# DC-DC_14V.net
KiCad netlist of a schematic drawn in Altium Designer
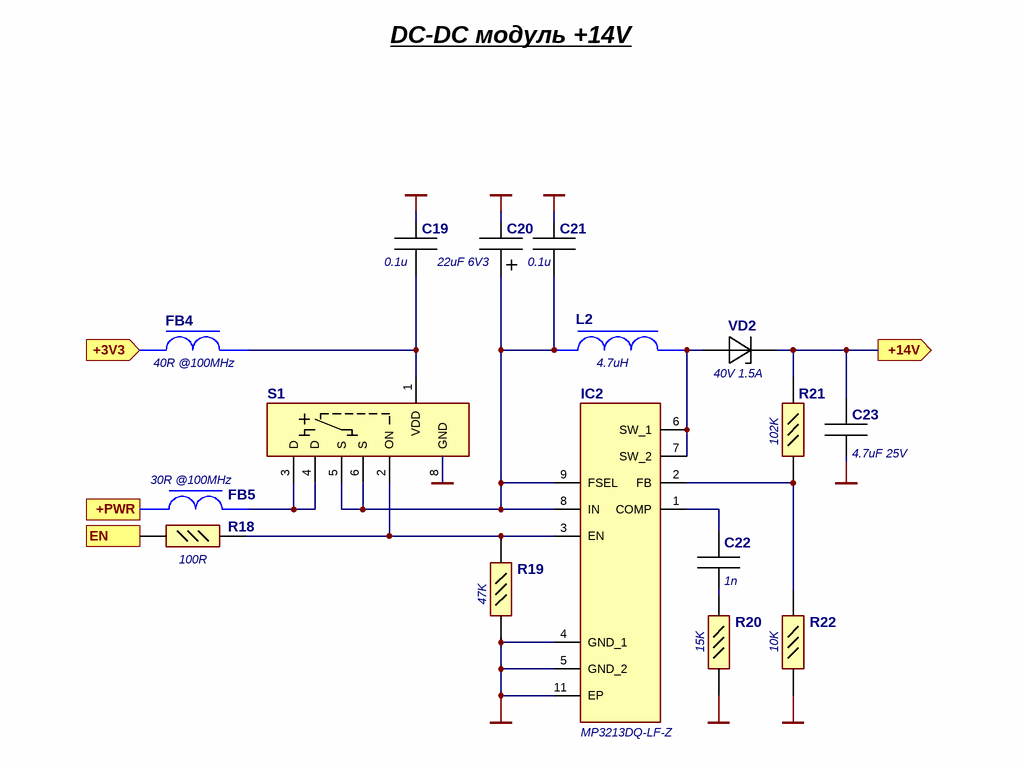
[diagram p0: DC-DC модуль +14V.SchDoc]

(export (version "E")
  (design (tool "Eeschema 10.0.6"))
  (components
    (comp (ref "C19")
      (value "0.1u")
      (footprint ":CAP0402 100x50x50")
      (description "±10% 25V Ceramic Capacitor X7R 0402 (1005 Metric)")
      (fields
        (field (name "MANUFACTURER_PART_NUMBER") "GRM155R71E104KE14J")
        (field (name "MOUSER PART NUMBER") "81-GRM155R71E104KE4J")
      )
      (libsource (lib "Capacitors 0402") (part "GRM155R71E104KE14J"))
    )
    (comp (ref "C20")
      (value "22uF 6V3")
      (footprint ":CAP1206 C3216-18")
      (description "22uF Molded Tantalum Capacitors 6.3V 1206 (3216 Metric) 300mOhm @ 100kHz")
      (fields (field (name "MANUFACTURER_PART_NUMBER") "TPSA226K006R0300"))
      (libsource (lib "Capacitors 1206") (part "TPSA226K006R0300"))
    )
    (comp (ref "C21")
      (value "0.1u")
      (footprint ":CAP0402 100x50x50")
      (description "±10% 25V Ceramic Capacitor X7R 0402 (1005 Metric)")
      (fields
        (field (name "MANUFACTURER_PART_NUMBER") "GRM155R71E104KE14J")
        (field (name "MOUSER PART NUMBER") "81-GRM155R71E104KE4J")
      )
      (libsource (lib "Capacitors 0402") (part "GRM155R71E104KE14J"))
    )
    (comp (ref "C22")
      (value "1n")
      (footprint ":CAP0402 100x50x50")
      (description "±5% 50V Ceramic Capacitor C0G, NP0 0402 (1005 Metric)")
      (fields (field (name "MANUFACTURER_PART_NUMBER") "GRM1555C1H102JA01J"))
      (libsource (lib "Capacitors 0402") (part "GRM1555C1H102JA01J"))
    )
    (comp (ref "C23")
      (value "4.7uF 25V")
      (footprint ":CAP0805 C2012X125")
      (description "CAP CER 4.7uF 25V X7R 0805")
      (fields (field (name "MANUFACTURER_PART_NUMBER") "GRM21BZ71E475KE15L"))
      (libsource (lib "Capacitors 0805") (part "GRM21BZ71E475KE15L"))
    )
    (comp (ref "FB4")
      (value "40R @100MHz")
      (footprint ":FER MMZ1005Y400CTD25")
      (description "40 Ohms @ 100MHz 1 Signal Line Ferrite Bead 0402 (1005 Metric) 550mA 100mOhm")
      (fields
        (field (name "MANUFACTURER_PART_NUMBER") "MMZ1005Y400CTD25")
        (field (name "MOUSER PART NUMBER") "810-MMZ1005Y400CTD25")
      )
      (libsource (lib "Ferrite Bead") (part "MMZ1005Y400CTD25"))
    )
    (comp (ref "FB5")
      (value "30R @100MHz")
      (footprint ":FER BLM18SP300SN1D")
      (description "30 Ohms @ 100MHz 1 Power Line Ferrite Bead 0603 (1608 Metric) 6A 8mOhm")
      (fields
        (field (name "MANUFACTURER_PART_NUMBER") "BLM18SP300SN1D")
        (field (name "MOUSER PART NUMBER") "81-BLM18SP300SN1D")
      )
      (libsource (lib "Ferrite Bead") (part "BLM18SP300SN1D"))
    )
    (comp (ref "IC2")
      (value "MP3213DQ-LF-Z")
      (footprint ":QFN10 P300X300X100-11N-D")
      (description "DC/DC Converter \r\n3...22V 3.5A")
      (fields (field (name "MOUSER PART NUMBER") "946-MP3213DQLFZ"))
      (libsource (lib "DC-DC convertors") (part "MP3213DQ-LF-Z"))
    )
    (comp (ref "L2")
      (value "4.7uH")
      (footprint ":IND1210 C3225")
      (fields (field (name "MANUFACTURER_PART_NUMBER") "CBC3225T4R7MR"))
      (libsource (lib "Inductance") (part "CBC3225T4R7MR"))
    )
    (comp (ref "R18")
      (value "RC0402FR-07")
      (footprint ":RES0402")
      (fields (field (name "MANUFACTURER_PART_NUMBER (PART 2: VALUE)") "100R"))
      (libsource (lib "") (part "RC0402FR-07_1"))
    )
    (comp (ref "R19")
      (value "RC0402FR-07")
      (footprint ":RES0402")
      (fields (field (name "MANUFACTURER_PART_NUMBER (PART 2: VALUE)") "47K"))
      (libsource (lib "Resistors 0402") (part "RC0402FR-07"))
    )
    (comp (ref "R20")
      (value "RC0402FR-07")
      (footprint ":RES0402")
      (fields (field (name "MANUFACTURER_PART_NUMBER (PART 2: VALUE)") "15K"))
      (libsource (lib "Resistors 0402") (part "RC0402FR-07"))
    )
    (comp (ref "R21")
      (value "RC0402FR-07")
      (footprint ":RES0402")
      (fields (field (name "MANUFACTURER_PART_NUMBER (PART 2: VALUE)") "102K"))
      (libsource (lib "Resistors 0402") (part "RC0402FR-07"))
    )
    (comp (ref "R22")
      (value "RC0402FR-07")
      (footprint ":RES0402")
      (fields (field (name "MANUFACTURER_PART_NUMBER (PART 2: VALUE)") "10K"))
      (libsource (lib "Resistors 0402") (part "RC0402FR-07"))
    )
    (comp (ref "S1")
      (value "4A 7.8mOhm")
      (footprint ":TRAN SLG59M309V")
      (description "Power Switch/Driver 1:1 N-Channel 4A  7.8mOhm 8-FC-TDFN (1.5x2)")
      (fields (field (name "MANUFACTURER_PART_NUMBER") "SLG59M309V"))
      (libsource (lib "Switching and Relays") (part "SLG59M309V"))
    )
    (comp (ref "VD2")
      (value "40V 1.5A")
      (footprint ":DIODE CST2C")
      (description "Diode Schottky 40V 1.5A\r\n@If 550mV @ 1.5A\r\n@Vr 200µA @ 40V")
      (fields (field (name "MANUFACTURER_PART_NUMBER") "CCS15S40,L3F"))
      (libsource (lib "Diodes 0603") (part "CCS15S40,L3F"))
    )
  )
  (nets
    (net (code "1") (name "/+3V3") (class "Default")
      (node (ref "FB4") (pin "2") (pinfunction "2_2") (pintype "passive"))
    )
    (net (code "2") (name "/+14V") (class "Default")
      (node (ref "C23") (pin "2") (pinfunction "2_2") (pintype "passive"))
      (node (ref "R21") (pin "2") (pinfunction "2_2") (pintype "passive"))
      (node (ref "VD2") (pin "1") (pinfunction "K_1") (pintype "passive"))
    )
    (net (code "3") (name "/+PWR") (class "Default")
      (node (ref "FB5") (pin "1") (pinfunction "1_1") (pintype "passive"))
    )
    (net (code "4") (name "/EN") (class "Default")
      (node (ref "R18") (pin "1") (pinfunction "1_1") (pintype "passive"))
    )
    (net (code "5") (name "GND") (class "Default")
      (node (ref "C19") (pin "1") (pinfunction "1_1") (pintype "passive"))
      (node (ref "C20") (pin "2") (pinfunction "2_2") (pintype "passive"))
      (node (ref "C21") (pin "1") (pinfunction "1_1") (pintype "passive"))
      (node (ref "C23") (pin "1") (pinfunction "1_1") (pintype "passive"))
      (node (ref "IC2") (pin "11") (pinfunction "EP_11") (pintype "passive"))
      (node (ref "IC2") (pin "4") (pinfunction "GND_1_4") (pintype "passive"))
      (node (ref "IC2") (pin "5") (pinfunction "GND_2_5") (pintype "passive"))
      (node (ref "R19") (pin "1") (pinfunction "1_1") (pintype "passive"))
      (node (ref "R20") (pin "1") (pinfunction "1_1") (pintype "passive"))
      (node (ref "R22") (pin "1") (pinfunction "1_1") (pintype "passive"))
      (node (ref "S1") (pin "8") (pinfunction "GND_8") (pintype "passive"))
    )
    (net (code "6") (name "Net-(C20-+)") (class "Default")
      (node (ref "C20") (pin "1") (pinfunction "+_1") (pintype "passive"))
      (node (ref "C21") (pin "2") (pinfunction "2_2") (pintype "passive"))
      (node (ref "IC2") (pin "8") (pinfunction "IN_8") (pintype "passive"))
      (node (ref "IC2") (pin "9") (pinfunction "FSEL_9") (pintype "passive"))
      (node (ref "L2") (pin "1") (pinfunction "1_1") (pintype "passive"))
      (node (ref "S1") (pin "5") (pinfunction "S_5") (pintype "passive"))
      (node (ref "S1") (pin "6") (pinfunction "S_6") (pintype "passive"))
    )
    (net (code "7") (name "Net-(C22-Pad1)") (class "Default")
      (node (ref "C22") (pin "1") (pinfunction "1_1") (pintype "passive"))
      (node (ref "R20") (pin "2") (pinfunction "2_2") (pintype "passive"))
    )
    (net (code "8") (name "Net-(FB5-Pad2)") (class "Default")
      (node (ref "FB5") (pin "2") (pinfunction "2_2") (pintype "passive"))
      (node (ref "S1") (pin "3") (pinfunction "D_3") (pintype "passive"))
      (node (ref "S1") (pin "4") (pinfunction "D_4") (pintype "passive"))
    )
    (net (code "9") (name "Net-(IC2-COMP)") (class "Default")
      (node (ref "C22") (pin "2") (pinfunction "2_2") (pintype "passive"))
      (node (ref "IC2") (pin "1") (pinfunction "COMP_1") (pintype "passive"))
    )
    (net (code "10") (name "Net-(IC2-EN)") (class "Default")
      (node (ref "IC2") (pin "3") (pinfunction "EN_3") (pintype "passive"))
      (node (ref "R18") (pin "2") (pinfunction "2_2") (pintype "passive"))
      (node (ref "R19") (pin "2") (pinfunction "2_2") (pintype "passive"))
      (node (ref "S1") (pin "2") (pinfunction "ON_2") (pintype "passive"))
    )
    (net (code "11") (name "Net-(IC2-FB)") (class "Default")
      (node (ref "IC2") (pin "2") (pinfunction "FB_2") (pintype "passive"))
      (node (ref "R21") (pin "1") (pinfunction "1_1") (pintype "passive"))
      (node (ref "R22") (pin "2") (pinfunction "2_2") (pintype "passive"))
    )
    (net (code "12") (name "Net-(IC2-SW_1)") (class "Default")
      (node (ref "IC2") (pin "6") (pinfunction "SW_1_6") (pintype "passive"))
      (node (ref "IC2") (pin "7") (pinfunction "SW_2_7") (pintype "passive"))
      (node (ref "L2") (pin "2") (pinfunction "2_2") (pintype "passive"))
      (node (ref "VD2") (pin "2") (pinfunction "A_2") (pintype "passive"))
    )
    (net (code "13") (name "Net-(S1-VDD)") (class "Default")
      (node (ref "C19") (pin "2") (pinfunction "2_2") (pintype "passive"))
      (node (ref "FB4") (pin "1") (pinfunction "1_1") (pintype "passive"))
      (node (ref "S1") (pin "1") (pinfunction "VDD_1") (pintype "passive"))
    )
  )
)
